# si473x_board.net
KiCad netlist of a schematic drawn in EAGLE
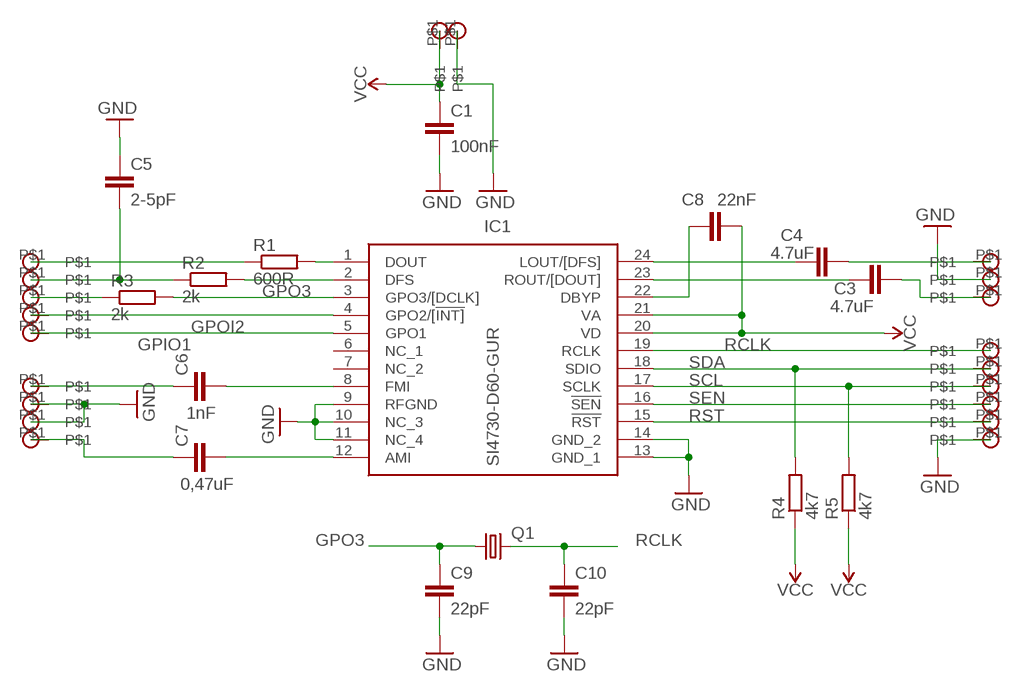
[diagram p0: schematic, sheet 1]

(export (version "E")
  (design (tool "Eeschema 10.0.6"))
  (components
    (comp (ref "AMI")
      (value "SMD_PIN")
      (footprint "eagle-import:SMD_PIN")
      (libsource (lib "eagle-import") (part "SMD_PIN"))
    )
    (comp (ref "C1")
      (value "100nF")
      (footprint "eagle-import:C0805")
      (libsource (lib "eagle-import") (part "C-EUC0805"))
    )
    (comp (ref "C3")
      (value "4.7uF")
      (footprint "eagle-import:C1210")
      (libsource (lib "eagle-import") (part "C-EUC1210"))
    )
    (comp (ref "C4")
      (value "4.7uF")
      (footprint "eagle-import:C1210")
      (libsource (lib "eagle-import") (part "C-EUC1210"))
    )
    (comp (ref "C5")
      (value "2-5pF")
      (footprint "eagle-import:C0805")
      (libsource (lib "eagle-import") (part "C-EUC0805"))
    )
    (comp (ref "C6")
      (value "1nF")
      (footprint "eagle-import:C0805")
      (libsource (lib "eagle-import") (part "C-EUC0805"))
    )
    (comp (ref "C7")
      (value "0,47uF")
      (footprint "eagle-import:C0805")
      (libsource (lib "eagle-import") (part "C-EUC0805"))
    )
    (comp (ref "C8")
      (value "22nF")
      (footprint "eagle-import:C0805")
      (libsource (lib "eagle-import") (part "C-EUC0805"))
    )
    (comp (ref "C9")
      (value "22pF")
      (footprint "eagle-import:C0805")
      (libsource (lib "eagle-import") (part "C-EUC0805"))
    )
    (comp (ref "C10")
      (value "22pF")
      (footprint "eagle-import:C0805")
      (libsource (lib "eagle-import") (part "C-EUC0805"))
    )
    (comp (ref "FMI")
      (value "SMD_PIN")
      (footprint "eagle-import:SMD_PIN")
      (libsource (lib "eagle-import") (part "SMD_PIN"))
    )
    (comp (ref "GND")
      (value "SMD_PIN")
      (footprint "eagle-import:SMD_PIN")
      (libsource (lib "eagle-import") (part "SMD_PIN"))
    )
    (comp (ref "IC1")
      (value "SI4730-D60-GUR")
      (footprint "eagle-import:SOP64P600X200-24N")
      (libsource (lib "eagle-import") (part "SI4730-D60-GUR"))
    )
    (comp (ref "Q1")
      (value "KX-327-NHF")
      (footprint "eagle-import:3.2X1.5")
      (libsource (lib "eagle-import") (part "KX-327-NHF"))
    )
    (comp (ref "R1")
      (value "600R")
      (footprint "eagle-import:R0805")
      (libsource (lib "eagle-import") (part "R-EU_R0805"))
    )
    (comp (ref "R2")
      (value "2k")
      (footprint "eagle-import:R0805")
      (libsource (lib "eagle-import") (part "R-EU_R0805"))
    )
    (comp (ref "R3")
      (value "2k")
      (footprint "eagle-import:R0805")
      (libsource (lib "eagle-import") (part "R-EU_R0805"))
    )
    (comp (ref "R4")
      (value "4k7")
      (footprint "eagle-import:0204_7")
      (libsource (lib "eagle-import") (part "R-EU_0204/7"))
    )
    (comp (ref "R5")
      (value "4k7")
      (footprint "eagle-import:0204_7")
      (libsource (lib "eagle-import") (part "R-EU_0204/7"))
    )
    (comp (ref "U$1")
      (value "SMD_PIN")
      (footprint "eagle-import:SMD_PIN")
      (libsource (lib "eagle-import") (part "SMD_PIN"))
    )
    (comp (ref "U$2")
      (value "SMD_PIN")
      (footprint "eagle-import:SMD_PIN")
      (libsource (lib "eagle-import") (part "SMD_PIN"))
    )
    (comp (ref "U$3")
      (value "SMD_PIN")
      (footprint "eagle-import:SMD_PIN")
      (libsource (lib "eagle-import") (part "SMD_PIN"))
    )
    (comp (ref "U$4")
      (value "SMD_PIN")
      (footprint "eagle-import:SMD_PIN")
      (libsource (lib "eagle-import") (part "SMD_PIN"))
    )
    (comp (ref "U$5")
      (value "SMD_PIN")
      (footprint "eagle-import:SMD_PIN")
      (libsource (lib "eagle-import") (part "SMD_PIN"))
    )
    (comp (ref "U$8")
      (value "SMD_PIN")
      (footprint "eagle-import:SMD_PIN")
      (libsource (lib "eagle-import") (part "SMD_PIN"))
    )
    (comp (ref "U$10")
      (value "SMD_PIN")
      (footprint "eagle-import:SMD_PIN")
      (libsource (lib "eagle-import") (part "SMD_PIN"))
    )
    (comp (ref "U$11")
      (value "SMD_PIN")
      (footprint "eagle-import:SMD_PIN")
      (libsource (lib "eagle-import") (part "SMD_PIN"))
    )
    (comp (ref "U$12")
      (value "SMD_PIN")
      (footprint "eagle-import:SMD_PIN")
      (libsource (lib "eagle-import") (part "SMD_PIN"))
    )
    (comp (ref "U$13")
      (value "SMD_PIN")
      (footprint "eagle-import:SMD_PIN")
      (libsource (lib "eagle-import") (part "SMD_PIN"))
    )
    (comp (ref "U$14")
      (value "SMD_PIN")
      (footprint "eagle-import:SMD_PIN")
      (libsource (lib "eagle-import") (part "SMD_PIN"))
    )
    (comp (ref "U$15")
      (value "SMD_PIN")
      (footprint "eagle-import:SMD_PIN")
      (libsource (lib "eagle-import") (part "SMD_PIN"))
    )
    (comp (ref "U$16")
      (value "SMD_PIN")
      (footprint "eagle-import:SMD_PIN")
      (libsource (lib "eagle-import") (part "SMD_PIN"))
    )
    (comp (ref "U$17")
      (value "SMD_PIN")
      (footprint "eagle-import:SMD_PIN")
      (libsource (lib "eagle-import") (part "SMD_PIN"))
    )
    (comp (ref "U$18")
      (value "SMD_PIN")
      (footprint "eagle-import:SMD_PIN")
      (libsource (lib "eagle-import") (part "SMD_PIN"))
    )
    (comp (ref "U$19")
      (value "SMD_PIN")
      (footprint "eagle-import:SMD_PIN")
      (libsource (lib "eagle-import") (part "SMD_PIN"))
    )
    (comp (ref "U$20")
      (value "SMD_PIN")
      (footprint "eagle-import:SMD_PIN")
      (libsource (lib "eagle-import") (part "SMD_PIN"))
    )
  )
  (nets
    (net (code "1") (name "/GPIO1") (class "Default")
      (node (ref "IC1") (pin "5") (pinfunction "GPO1_5") (pintype "bidirectional"))
      (node (ref "U$5") (pin "P$1") (pinfunction "P$1_P$1") (pintype "bidirectional"))
    )
    (net (code "2") (name "/GPO3") (class "Default")
      (node (ref "C9") (pin "1") (pinfunction "1_1") (pintype "passive"))
      (node (ref "IC1") (pin "3") (pinfunction "GPO3/[DCLK]_3") (pintype "bidirectional"))
      (node (ref "Q1") (pin "1") (pinfunction "1_1") (pintype "passive"))
      (node (ref "R3") (pin "2") (pinfunction "2_2") (pintype "passive"))
    )
    (net (code "3") (name "/GPOI2") (class "Default")
      (node (ref "IC1") (pin "4") (pinfunction "GPO2/[~{INT]}_4") (pintype "bidirectional"))
      (node (ref "U$4") (pin "P$1") (pinfunction "P$1_P$1") (pintype "bidirectional"))
    )
    (net (code "4") (name "/RCLK") (class "Default")
      (node (ref "C10") (pin "1") (pinfunction "1_1") (pintype "passive"))
      (node (ref "IC1") (pin "19") (pinfunction "RCLK_19") (pintype "bidirectional"))
      (node (ref "Q1") (pin "2") (pinfunction "2_2") (pintype "passive"))
      (node (ref "U$15") (pin "P$1") (pinfunction "P$1_P$1") (pintype "bidirectional"))
    )
    (net (code "5") (name "/RST") (class "Default")
      (node (ref "IC1") (pin "15") (pinfunction "~{RST}_15") (pintype "bidirectional"))
      (node (ref "U$19") (pin "P$1") (pinfunction "P$1_P$1") (pintype "bidirectional"))
    )
    (net (code "6") (name "/SCL") (class "Default")
      (node (ref "IC1") (pin "17") (pinfunction "SCLK_17") (pintype "bidirectional"))
      (node (ref "R5") (pin "2") (pinfunction "2_2") (pintype "passive"))
      (node (ref "U$17") (pin "P$1") (pinfunction "P$1_P$1") (pintype "bidirectional"))
    )
    (net (code "7") (name "/SDA") (class "Default")
      (node (ref "IC1") (pin "18") (pinfunction "SDIO_18") (pintype "bidirectional"))
      (node (ref "R4") (pin "2") (pinfunction "2_2") (pintype "passive"))
      (node (ref "U$16") (pin "P$1") (pinfunction "P$1_P$1") (pintype "bidirectional"))
    )
    (net (code "8") (name "/SEN") (class "Default")
      (node (ref "IC1") (pin "16") (pinfunction "~{SEN}_16") (pintype "bidirectional"))
      (node (ref "U$18") (pin "P$1") (pinfunction "P$1_P$1") (pintype "bidirectional"))
    )
    (net (code "9") (name "GND") (class "Default")
      (node (ref "C1") (pin "2") (pinfunction "2_2") (pintype "passive"))
      (node (ref "C10") (pin "2") (pinfunction "2_2") (pintype "passive"))
      (node (ref "C5") (pin "1") (pinfunction "1_1") (pintype "passive"))
      (node (ref "C9") (pin "2") (pinfunction "2_2") (pintype "passive"))
      (node (ref "GND") (pin "P$1") (pinfunction "P$1_P$1") (pintype "bidirectional"))
      (node (ref "IC1") (pin "10") (pinfunction "NC_3_10") (pintype "bidirectional"))
      (node (ref "IC1") (pin "11") (pinfunction "NC_4_11") (pintype "bidirectional"))
      (node (ref "IC1") (pin "13") (pinfunction "GND_1_13") (pintype "bidirectional"))
      (node (ref "IC1") (pin "14") (pinfunction "GND_2_14") (pintype "bidirectional"))
      (node (ref "IC1") (pin "9") (pinfunction "RFGND_9") (pintype "bidirectional"))
      (node (ref "U$11") (pin "P$1") (pinfunction "P$1_P$1") (pintype "bidirectional"))
      (node (ref "U$13") (pin "P$1") (pinfunction "P$1_P$1") (pintype "bidirectional"))
      (node (ref "U$20") (pin "P$1") (pinfunction "P$1_P$1") (pintype "bidirectional"))
      (node (ref "U$8") (pin "P$1") (pinfunction "P$1_P$1") (pintype "bidirectional"))
    )
    (net (code "10") (name "Net-(AMI-PadP$1)") (class "Default")
      (node (ref "AMI") (pin "P$1") (pinfunction "P$1_P$1") (pintype "bidirectional"))
      (node (ref "C7") (pin "1") (pinfunction "1_1") (pintype "passive"))
    )
    (net (code "11") (name "Net-(C3-Pad2)") (class "Default")
      (node (ref "C3") (pin "2") (pinfunction "2_2") (pintype "passive"))
      (node (ref "U$14") (pin "P$1") (pinfunction "P$1_P$1") (pintype "bidirectional"))
    )
    (net (code "12") (name "Net-(C4-Pad2)") (class "Default")
      (node (ref "C4") (pin "2") (pinfunction "2_2") (pintype "passive"))
      (node (ref "U$12") (pin "P$1") (pinfunction "P$1_P$1") (pintype "bidirectional"))
    )
    (net (code "13") (name "Net-(C5-Pad2)") (class "Default")
      (node (ref "C5") (pin "2") (pinfunction "2_2") (pintype "passive"))
      (node (ref "R2") (pin "1") (pinfunction "1_1") (pintype "passive"))
      (node (ref "U$2") (pin "P$1") (pinfunction "P$1_P$1") (pintype "bidirectional"))
    )
    (net (code "14") (name "Net-(C6-Pad1)") (class "Default")
      (node (ref "C6") (pin "1") (pinfunction "1_1") (pintype "passive"))
      (node (ref "FMI") (pin "P$1") (pinfunction "P$1_P$1") (pintype "bidirectional"))
    )
    (net (code "15") (name "Net-(IC1-AMI)") (class "Default")
      (node (ref "C7") (pin "2") (pinfunction "2_2") (pintype "passive"))
      (node (ref "IC1") (pin "12") (pinfunction "AMI_12") (pintype "bidirectional"))
    )
    (net (code "16") (name "Net-(IC1-DBYP)") (class "Default")
      (node (ref "C8") (pin "2") (pinfunction "2_2") (pintype "passive"))
      (node (ref "IC1") (pin "22") (pinfunction "DBYP_22") (pintype "bidirectional"))
    )
    (net (code "17") (name "Net-(IC1-DFS)") (class "Default")
      (node (ref "IC1") (pin "2") (pinfunction "DFS_2") (pintype "bidirectional"))
      (node (ref "R2") (pin "2") (pinfunction "2_2") (pintype "passive"))
    )
    (net (code "18") (name "Net-(IC1-DOUT)") (class "Default")
      (node (ref "IC1") (pin "1") (pinfunction "DOUT_1") (pintype "bidirectional"))
      (node (ref "R1") (pin "2") (pinfunction "2_2") (pintype "passive"))
    )
    (net (code "19") (name "Net-(IC1-FMI)") (class "Default")
      (node (ref "C6") (pin "2") (pinfunction "2_2") (pintype "passive"))
      (node (ref "IC1") (pin "8") (pinfunction "FMI_8") (pintype "bidirectional"))
    )
    (net (code "20") (name "Net-(IC1-LOUT{slash}[DFS])") (class "Default")
      (node (ref "C4") (pin "1") (pinfunction "1_1") (pintype "passive"))
      (node (ref "IC1") (pin "24") (pinfunction "LOUT/[DFS]_24") (pintype "bidirectional"))
    )
    (net (code "21") (name "Net-(IC1-ROUT{slash}[DOUT])") (class "Default")
      (node (ref "C3") (pin "1") (pinfunction "1_1") (pintype "passive"))
      (node (ref "IC1") (pin "23") (pinfunction "ROUT/[DOUT]_23") (pintype "bidirectional"))
    )
    (net (code "22") (name "Net-(R1-Pad1)") (class "Default")
      (node (ref "R1") (pin "1") (pinfunction "1_1") (pintype "passive"))
      (node (ref "U$1") (pin "P$1") (pinfunction "P$1_P$1") (pintype "bidirectional"))
    )
    (net (code "23") (name "Net-(R3-Pad1)") (class "Default")
      (node (ref "R3") (pin "1") (pinfunction "1_1") (pintype "passive"))
      (node (ref "U$3") (pin "P$1") (pinfunction "P$1_P$1") (pintype "bidirectional"))
    )
    (net (code "24") (name "VCC") (class "Default")
      (node (ref "C1") (pin "1") (pinfunction "1_1") (pintype "passive"))
      (node (ref "C8") (pin "1") (pinfunction "1_1") (pintype "passive"))
      (node (ref "IC1") (pin "20") (pinfunction "VD_20") (pintype "bidirectional"))
      (node (ref "IC1") (pin "21") (pinfunction "VA_21") (pintype "bidirectional"))
      (node (ref "R4") (pin "1") (pinfunction "1_1") (pintype "passive"))
      (node (ref "R5") (pin "1") (pinfunction "1_1") (pintype "passive"))
      (node (ref "U$10") (pin "P$1") (pinfunction "P$1_P$1") (pintype "bidirectional"))
    )
    (net (code "25") (name "unconnected-(IC1-NC_1-Pad6)") (class "Default")
      (node (ref "IC1") (pin "6") (pinfunction "NC_1_6") (pintype "bidirectional"))
    )
    (net (code "26") (name "unconnected-(IC1-NC_2-Pad7)") (class "Default")
      (node (ref "IC1") (pin "7") (pinfunction "NC_2_7") (pintype "bidirectional"))
    )
  )
)
